# PCB.net
KiCad netlist of a schematic drawn in EasyEDA Pro
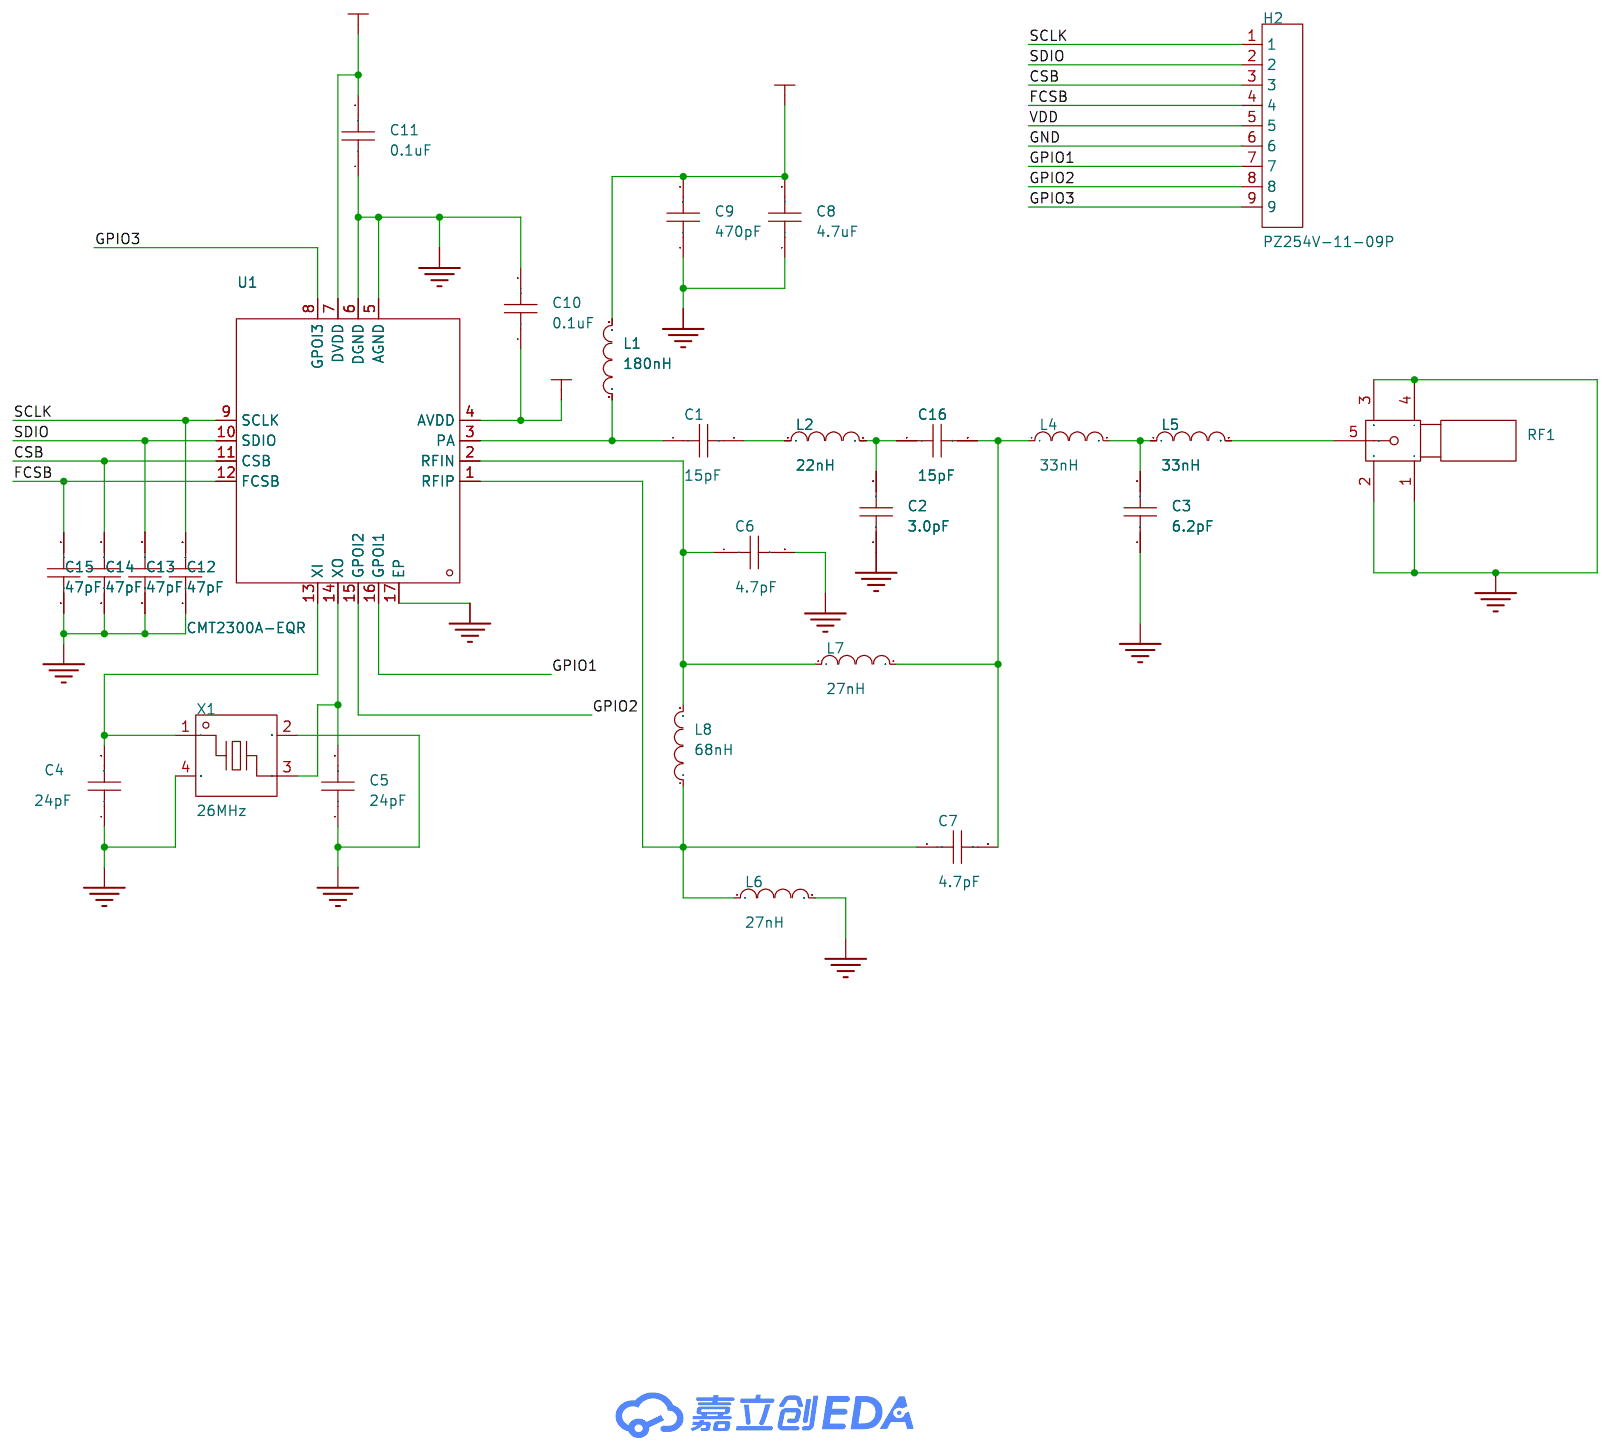
[diagram p0: schematic sheet]

(export (version "E")
  (design (tool "Eeschema 10.0.6"))
  (components
    (comp (ref "C1")
      (value "15pF")
      (footprint "easyedapro:C0603")
      (libsource (lib "easyedapro") (part "Capacitance"))
    )
    (comp (ref "C2")
      (value "3.0pF")
      (footprint "easyedapro:C0603")
      (libsource (lib "easyedapro") (part "Capacitance"))
    )
    (comp (ref "C3")
      (value "6.2pF")
      (footprint "easyedapro:C0603")
      (libsource (lib "easyedapro") (part "Capacitance"))
    )
    (comp (ref "C4")
      (value "24pF")
      (footprint "easyedapro:C0603")
      (libsource (lib "easyedapro") (part "Capacitance"))
    )
    (comp (ref "C5")
      (value "24pF")
      (footprint "easyedapro:C0603")
      (libsource (lib "easyedapro") (part "Capacitance"))
    )
    (comp (ref "C6")
      (value "4.7pF")
      (footprint "easyedapro:C0603")
      (libsource (lib "easyedapro") (part "Capacitance"))
    )
    (comp (ref "C7")
      (value "4.7pF")
      (footprint "easyedapro:C0603")
      (libsource (lib "easyedapro") (part "Capacitance"))
    )
    (comp (ref "C8")
      (value "4.7uF")
      (footprint "easyedapro:C0603")
      (libsource (lib "easyedapro") (part "Capacitance"))
    )
    (comp (ref "C9")
      (value "470pF")
      (footprint "easyedapro:C0603")
      (libsource (lib "easyedapro") (part "Capacitance"))
    )
    (comp (ref "C10")
      (value "0.1uF")
      (footprint "easyedapro:C0603")
      (libsource (lib "easyedapro") (part "Capacitance"))
    )
    (comp (ref "C11")
      (value "0.1uF")
      (footprint "easyedapro:C0603")
      (libsource (lib "easyedapro") (part "Capacitance"))
    )
    (comp (ref "C12")
      (value "47pF")
      (footprint "easyedapro:C0603")
      (libsource (lib "easyedapro") (part "Capacitance"))
    )
    (comp (ref "C13")
      (value "47pF")
      (footprint "easyedapro:C0603")
      (libsource (lib "easyedapro") (part "Capacitance"))
    )
    (comp (ref "C14")
      (value "47pF")
      (footprint "easyedapro:C0603")
      (libsource (lib "easyedapro") (part "Capacitance"))
    )
    (comp (ref "C15")
      (value "47pF")
      (footprint "easyedapro:C0603")
      (libsource (lib "easyedapro") (part "Capacitance"))
    )
    (comp (ref "C16")
      (value "15pF")
      (footprint "easyedapro:C0603")
      (libsource (lib "easyedapro") (part "Capacitance"))
    )
    (comp (ref "H2")
      (value "PZ254V-11-09P")
      (footprint "easyedapro:HDR-TH_9P-P2.54-V-M")
      (fields (field (name "Manufacturer") "XFCN(兴飞)"))
      (libsource (lib "easyedapro") (part "PZ254V-11-09P"))
    )
    (comp (ref "L1")
      (value "180nH")
      (footprint "easyedapro:L0603")
      (libsource (lib "easyedapro") (part "SDFL1608S100KTF"))
    )
    (comp (ref "L2")
      (value "22nH")
      (footprint "easyedapro:L0603")
      (libsource (lib "easyedapro") (part "SDFL1608S100KTF"))
    )
    (comp (ref "L4")
      (value "33nH")
      (footprint "easyedapro:L0603")
      (libsource (lib "easyedapro") (part "SDFL1608S100KTF"))
    )
    (comp (ref "L5")
      (value "33nH")
      (footprint "easyedapro:L0603")
      (libsource (lib "easyedapro") (part "SDFL1608S100KTF"))
    )
    (comp (ref "L6")
      (value "27nH")
      (footprint "easyedapro:L0603")
      (libsource (lib "easyedapro") (part "SDFL1608S100KTF"))
    )
    (comp (ref "L7")
      (value "27nH")
      (footprint "easyedapro:L0603")
      (libsource (lib "easyedapro") (part "SDFL1608S100KTF"))
    )
    (comp (ref "L8")
      (value "68nH")
      (footprint "easyedapro:L0603")
      (libsource (lib "easyedapro") (part "SDFL1608S100KTF"))
    )
    (comp (ref "RF1")
      (value "-")
      (footprint "easyedapro:SMA-TH_BWSMA-KE-Z001")
      (description "连接器类型:板端;接口类型:内孔;端口数量:1;接口直径:-;接口长度/高度:-;频率:-;射频系列:SMA;阻抗:50Ω;样式:正脚;工作温度:-65°C~+165°C;")
      (fields
        (field (name "Manufacturer Part") "BWSMA-KE-Z001")
        (field (name "Manufacturer") "BAT WIRELESS(蝙蝠无线)")
      )
      (libsource (lib "easyedapro") (part "BWSMA-KE-Z001"))
    )
    (comp (ref "U1")
      (value "CMT2300A-EQR")
      (footprint "easyedapro:QFN-16_L3.0-W3.0-P0.50-BL-EP1.7")
      (description "频率范围:127MHz~1.02GHz;接口类型:SPI;应用领域:ISM;数据速率:300Kbps;灵敏度:-121dBm;典型应用频率:433.92MHz;")
      (fields (field (name "Manufacturer") "HOPERF(华普微电子)"))
      (libsource (lib "easyedapro") (part "CMT2300A-EQR"))
    )
    (comp (ref "X1")
      (value "26MHz")
      (footprint "easyedapro:CRYSTAL-SMD_4P-L3.2-W2.5-BL")
      (description "晶振类型:贴片晶振;频率:26MHz;常温频差:±10ppm;负载电容:15pF;频率稳定度:±15ppm;")
      (fields (field (name "Manufacturer Part") "TAXM26M4RHBCCT2T") (field (name "Manufacturer") "YJX(雅晶鑫)"))
      (libsource (lib "easyedapro") (part "TAXM26M4RHBCCT2T"))
    )
  )
  (nets
    (net (code "1") (name "/CSB") (class "Default")
      (node (ref "C14") (pin "2") (pinfunction "2_2") (pintype "input"))
      (node (ref "H2") (pin "3") (pinfunction "3_3") (pintype "unspecified"))
      (node (ref "U1") (pin "11") (pinfunction "CSB_11") (pintype "unspecified"))
    )
    (net (code "2") (name "/FCSB") (class "Default")
      (node (ref "C15") (pin "2") (pinfunction "2_2") (pintype "input"))
      (node (ref "H2") (pin "4") (pinfunction "4_4") (pintype "unspecified"))
      (node (ref "U1") (pin "12") (pinfunction "FCSB_12") (pintype "unspecified"))
    )
    (net (code "3") (name "/GPIO1") (class "Default")
      (node (ref "H2") (pin "7") (pinfunction "7_7") (pintype "unspecified"))
      (node (ref "U1") (pin "16") (pinfunction "GPOI1_16") (pintype "unspecified"))
    )
    (net (code "4") (name "/GPIO2") (class "Default")
      (node (ref "H2") (pin "8") (pinfunction "8_8") (pintype "unspecified"))
      (node (ref "U1") (pin "15") (pinfunction "GPOI2_15") (pintype "unspecified"))
    )
    (net (code "5") (name "/GPIO3") (class "Default")
      (node (ref "H2") (pin "9") (pinfunction "9_9") (pintype "unspecified"))
      (node (ref "U1") (pin "8") (pinfunction "GPOI3_8") (pintype "unspecified"))
    )
    (net (code "6") (name "/SCLK") (class "Default")
      (node (ref "C12") (pin "2") (pinfunction "2_2") (pintype "input"))
      (node (ref "H2") (pin "1") (pinfunction "1_1") (pintype "unspecified"))
      (node (ref "U1") (pin "9") (pinfunction "SCLK_9") (pintype "unspecified"))
    )
    (net (code "7") (name "/SDIO") (class "Default")
      (node (ref "C13") (pin "2") (pinfunction "2_2") (pintype "input"))
      (node (ref "H2") (pin "2") (pinfunction "2_2") (pintype "unspecified"))
      (node (ref "U1") (pin "10") (pinfunction "SDIO_10") (pintype "unspecified"))
    )
    (net (code "8") (name "GND") (class "Default")
      (node (ref "C10") (pin "2") (pinfunction "2_2") (pintype "input"))
      (node (ref "C11") (pin "1") (pinfunction "1_1") (pintype "input"))
      (node (ref "C12") (pin "1") (pinfunction "1_1") (pintype "input"))
      (node (ref "C13") (pin "1") (pinfunction "1_1") (pintype "input"))
      (node (ref "C14") (pin "1") (pinfunction "1_1") (pintype "input"))
      (node (ref "C15") (pin "1") (pinfunction "1_1") (pintype "input"))
      (node (ref "C2") (pin "1") (pinfunction "1_1") (pintype "input"))
      (node (ref "C3") (pin "1") (pinfunction "1_1") (pintype "input"))
      (node (ref "C4") (pin "1") (pinfunction "1_1") (pintype "input"))
      (node (ref "C5") (pin "1") (pinfunction "1_1") (pintype "input"))
      (node (ref "C6") (pin "2") (pinfunction "2_2") (pintype "input"))
      (node (ref "C8") (pin "1") (pinfunction "1_1") (pintype "input"))
      (node (ref "C9") (pin "1") (pinfunction "1_1") (pintype "input"))
      (node (ref "H2") (pin "6") (pinfunction "6_6") (pintype "unspecified"))
      (node (ref "L6") (pin "2") (pinfunction "2_2") (pintype "unspecified"))
      (node (ref "RF1") (pin "1") (pinfunction "1_1") (pintype "unspecified"))
      (node (ref "RF1") (pin "2") (pinfunction "2_2") (pintype "unspecified"))
      (node (ref "RF1") (pin "3") (pinfunction "3_3") (pintype "unspecified"))
      (node (ref "RF1") (pin "4") (pinfunction "4_4") (pintype "unspecified"))
      (node (ref "U1") (pin "17") (pinfunction "EP_17") (pintype "unspecified"))
      (node (ref "U1") (pin "5") (pinfunction "AGND_5") (pintype "unspecified"))
      (node (ref "U1") (pin "6") (pinfunction "DGND_6") (pintype "unspecified"))
      (node (ref "X1") (pin "2") (pinfunction "GND_2") (pintype "input"))
      (node (ref "X1") (pin "4") (pinfunction "GND_4") (pintype "input"))
    )
    (net (code "9") (name "Net-(C1-Pad2)") (class "Default")
      (node (ref "C1") (pin "2") (pinfunction "2_2") (pintype "input"))
      (node (ref "L2") (pin "1") (pinfunction "1_1") (pintype "unspecified"))
    )
    (net (code "10") (name "Net-(C3-Pad2)") (class "Default")
      (node (ref "C3") (pin "2") (pinfunction "2_2") (pintype "input"))
      (node (ref "L4") (pin "2") (pinfunction "2_2") (pintype "unspecified"))
      (node (ref "L5") (pin "1") (pinfunction "1_1") (pintype "unspecified"))
    )
    (net (code "11") (name "Net-(C16-Pad1)") (class "Default")
      (node (ref "C16") (pin "1") (pinfunction "1_1") (pintype "input"))
      (node (ref "C2") (pin "2") (pinfunction "2_2") (pintype "input"))
      (node (ref "L2") (pin "2") (pinfunction "2_2") (pintype "unspecified"))
    )
    (net (code "12") (name "Net-(C16-Pad2)") (class "Default")
      (node (ref "C16") (pin "2") (pinfunction "2_2") (pintype "input"))
      (node (ref "C7") (pin "2") (pinfunction "2_2") (pintype "input"))
      (node (ref "L4") (pin "1") (pinfunction "1_1") (pintype "unspecified"))
      (node (ref "L7") (pin "2") (pinfunction "2_2") (pintype "unspecified"))
    )
    (net (code "13") (name "Net-(L5-Pad2)") (class "Default")
      (node (ref "L5") (pin "2") (pinfunction "2_2") (pintype "unspecified"))
      (node (ref "RF1") (pin "5") (pinfunction "5_5") (pintype "unspecified"))
    )
    (net (code "14") (name "Net-(U1-PA)") (class "Default")
      (node (ref "C1") (pin "1") (pinfunction "1_1") (pintype "input"))
      (node (ref "L1") (pin "1") (pinfunction "1_1") (pintype "unspecified"))
      (node (ref "U1") (pin "3") (pinfunction "PA_3") (pintype "unspecified"))
    )
    (net (code "15") (name "Net-(U1-RFIN)") (class "Default")
      (node (ref "C6") (pin "1") (pinfunction "1_1") (pintype "input"))
      (node (ref "L7") (pin "1") (pinfunction "1_1") (pintype "unspecified"))
      (node (ref "L8") (pin "2") (pinfunction "2_2") (pintype "unspecified"))
      (node (ref "U1") (pin "2") (pinfunction "RFIN_2") (pintype "unspecified"))
    )
    (net (code "16") (name "Net-(U1-RFIP)") (class "Default")
      (node (ref "C7") (pin "1") (pinfunction "1_1") (pintype "input"))
      (node (ref "L6") (pin "1") (pinfunction "1_1") (pintype "unspecified"))
      (node (ref "L8") (pin "1") (pinfunction "1_1") (pintype "unspecified"))
      (node (ref "U1") (pin "1") (pinfunction "RFIP_1") (pintype "unspecified"))
    )
    (net (code "17") (name "Net-(U1-XI)") (class "Default")
      (node (ref "C4") (pin "2") (pinfunction "2_2") (pintype "input"))
      (node (ref "U1") (pin "13") (pinfunction "XI_13") (pintype "unspecified"))
      (node (ref "X1") (pin "1") (pinfunction "1_1") (pintype "input"))
    )
    (net (code "18") (name "Net-(U1-XO)") (class "Default")
      (node (ref "C5") (pin "2") (pinfunction "2_2") (pintype "input"))
      (node (ref "U1") (pin "14") (pinfunction "XO_14") (pintype "unspecified"))
      (node (ref "X1") (pin "3") (pinfunction "3_3") (pintype "input"))
    )
    (net (code "19") (name "VDD") (class "Default")
      (node (ref "C10") (pin "1") (pinfunction "1_1") (pintype "input"))
      (node (ref "C11") (pin "2") (pinfunction "2_2") (pintype "input"))
      (node (ref "C8") (pin "2") (pinfunction "2_2") (pintype "input"))
      (node (ref "C9") (pin "2") (pinfunction "2_2") (pintype "input"))
      (node (ref "H2") (pin "5") (pinfunction "5_5") (pintype "unspecified"))
      (node (ref "L1") (pin "2") (pinfunction "2_2") (pintype "unspecified"))
      (node (ref "U1") (pin "4") (pinfunction "AVDD_4") (pintype "unspecified"))
      (node (ref "U1") (pin "7") (pinfunction "DVDD_7") (pintype "unspecified"))
    )
  )
)
